# piezo-buffer-and-preamp-ritter_V0-4-thru.net
KiCad netlist of a schematic drawn in EAGLE
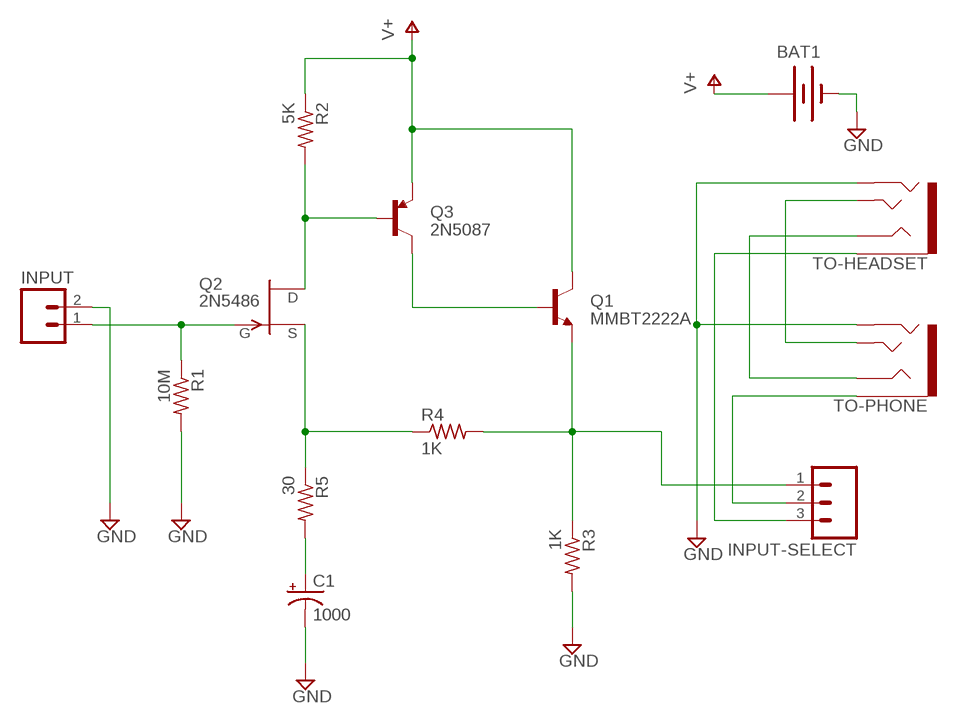
[diagram p0: schematic, sheet 1]

(export (version "E")
  (design (tool "Eeschema 10.0.6"))
  (components
    (comp (ref "BAT1")
      (value "BATTERYAAA-KIT")
      (footprint "eagle-import:BATTERY-AAA-KIT")
      (libsource (lib "eagle-import") (part "BATTERYAAA-KIT"))
    )
    (comp (ref "C1")
      (value "1000")
      (footprint "eagle-import:CPOL-RADIAL-1000UF-25V")
      (libsource (lib "eagle-import") (part "CAP_POLPTH4"))
    )
    (comp (ref "INPUT")
      (value "M02LOCK")
      (footprint "eagle-import:1X02_LOCK")
      (libsource (lib "eagle-import") (part "M02LOCK"))
    )
    (comp (ref "INPUT-SELECT")
      (value "M03LOCK")
      (footprint "eagle-import:1X03_LOCK")
      (libsource (lib "eagle-import") (part "M03LOCK"))
    )
    (comp (ref "Q1")
      (value "MMBT2222A")
      (footprint "eagle-import:TO-92")
      (libsource (lib "eagle-import") (part "TRANSISTOR_NPNTO92"))
    )
    (comp (ref "Q2")
      (value "2N5486")
      (footprint "eagle-import:TO92-")
      (libsource (lib "eagle-import") (part "?5482N6"))
    )
    (comp (ref "Q3")
      (value "2N5087")
      (footprint "eagle-import:TO-92")
      (libsource (lib "eagle-import") (part "TRANSISTOR_PNPTO92"))
    )
    (comp (ref "R1")
      (value "10M")
      (footprint "eagle-import:V526-0")
      (libsource (lib "eagle-import") (part "R-US_V526-0"))
    )
    (comp (ref "R2")
      (value "5K")
      (footprint "eagle-import:V526-0")
      (libsource (lib "eagle-import") (part "R-US_V526-0"))
    )
    (comp (ref "R3")
      (value "1K")
      (footprint "eagle-import:V526-0")
      (libsource (lib "eagle-import") (part "R-US_V526-0"))
    )
    (comp (ref "R4")
      (value "1K")
      (footprint "eagle-import:V526-0")
      (libsource (lib "eagle-import") (part "R-US_V526-0"))
    )
    (comp (ref "R5")
      (value "30")
      (footprint "eagle-import:V526-0")
      (libsource (lib "eagle-import") (part "R-US_V526-0"))
    )
    (comp (ref "TO-HEADSET")
      (value "AUDIO-JACK3")
      (footprint "eagle-import:AUDIO-JACK-TRRS-SMD")
      (libsource (lib "eagle-import") (part "AUDIO-JACK3"))
    )
    (comp (ref "TO-PHONE")
      (value "AUDIO-JACK3")
      (footprint "eagle-import:AUDIO-JACK-TRRS-SMD")
      (libsource (lib "eagle-import") (part "AUDIO-JACK3"))
    )
  )
  (nets
    (net (code "1") (name "GND") (class "Default")
      (node (ref "BAT1") (pin "GND@1") (pinfunction "-_GND@1") (pintype "power_in"))
      (node (ref "C1") (pin "-") (pinfunction "-_-") (pintype "passive"))
      (node (ref "INPUT") (pin "2") (pinfunction "2_2") (pintype "passive"))
      (node (ref "R1") (pin "2") (pinfunction "2_2") (pintype "passive"))
      (node (ref "R3") (pin "2") (pinfunction "2_2") (pintype "passive"))
      (node (ref "TO-HEADSET") (pin "RING2") (pinfunction "RING2_RING2") (pintype "bidirectional"))
      (node (ref "TO-PHONE") (pin "RING2") (pinfunction "RING2_RING2") (pintype "bidirectional"))
    )
    (net (code "2") (name "Net-(C1-Pad+)") (class "Default")
      (node (ref "C1") (pin "+") (pinfunction "+_+") (pintype "passive"))
      (node (ref "R5") (pin "2") (pinfunction "2_2") (pintype "passive"))
    )
    (net (code "3") (name "Net-(INPUT-SELECT-Pad2)") (class "Default")
      (node (ref "INPUT-SELECT") (pin "2") (pinfunction "2_2") (pintype "passive"))
      (node (ref "TO-PHONE") (pin "EARTH") (pinfunction "EARTH_EARTH") (pintype "bidirectional"))
    )
    (net (code "4") (name "Net-(INPUT-SELECT-Pad3)") (class "Default")
      (node (ref "INPUT-SELECT") (pin "3") (pinfunction "3_3") (pintype "passive"))
      (node (ref "TO-HEADSET") (pin "EARTH") (pinfunction "EARTH_EARTH") (pintype "bidirectional"))
    )
    (net (code "5") (name "Net-(Q1-B)") (class "Default")
      (node (ref "Q1") (pin "2") (pinfunction "B_2") (pintype "passive"))
      (node (ref "Q3") (pin "3") (pinfunction "C_3") (pintype "passive"))
    )
    (net (code "6") (name "Net-(Q1-E)") (class "Default")
      (node (ref "INPUT-SELECT") (pin "1") (pinfunction "1_1") (pintype "passive"))
      (node (ref "Q1") (pin "1") (pinfunction "E_1") (pintype "passive"))
      (node (ref "R3") (pin "1") (pinfunction "1_1") (pintype "passive"))
      (node (ref "R4") (pin "2") (pinfunction "2_2") (pintype "passive"))
    )
    (net (code "7") (name "Net-(Q2-D)") (class "Default")
      (node (ref "Q2") (pin "3") (pinfunction "D_3") (pintype "passive"))
      (node (ref "Q3") (pin "2") (pinfunction "B_2") (pintype "passive"))
      (node (ref "R2") (pin "2") (pinfunction "2_2") (pintype "passive"))
    )
    (net (code "8") (name "Net-(Q2-G)") (class "Default")
      (node (ref "INPUT") (pin "1") (pinfunction "1_1") (pintype "passive"))
      (node (ref "Q2") (pin "1") (pinfunction "G_1") (pintype "passive"))
      (node (ref "R1") (pin "1") (pinfunction "1_1") (pintype "passive"))
    )
    (net (code "9") (name "Net-(Q2-S)") (class "Default")
      (node (ref "Q2") (pin "2") (pinfunction "S_2") (pintype "passive"))
      (node (ref "R4") (pin "1") (pinfunction "1_1") (pintype "passive"))
      (node (ref "R5") (pin "1") (pinfunction "1_1") (pintype "passive"))
    )
    (net (code "10") (name "Net-(TO-HEADSET-PadRING1)") (class "Default")
      (node (ref "TO-HEADSET") (pin "RING1") (pinfunction "RING1_RING1") (pintype "bidirectional"))
      (node (ref "TO-PHONE") (pin "RING1") (pinfunction "RING1_RING1") (pintype "bidirectional"))
    )
    (net (code "11") (name "Net-(TO-HEADSET-PadTIP)") (class "Default")
      (node (ref "TO-HEADSET") (pin "TIP") (pinfunction "TIP_TIP") (pintype "bidirectional"))
      (node (ref "TO-PHONE") (pin "TIP") (pinfunction "TIP_TIP") (pintype "bidirectional"))
    )
    (net (code "12") (name "V+") (class "Default")
      (node (ref "BAT1") (pin "PWR@1") (pinfunction "+_PWR@1") (pintype "power_in"))
      (node (ref "Q1") (pin "3") (pinfunction "C_3") (pintype "passive"))
      (node (ref "Q3") (pin "1") (pinfunction "E_1") (pintype "passive"))
      (node (ref "R2") (pin "1") (pinfunction "1_1") (pintype "passive"))
    )
  )
)
